# FPGA_SDRAM.net
KiCad netlist of a schematic drawn in Altium Designer
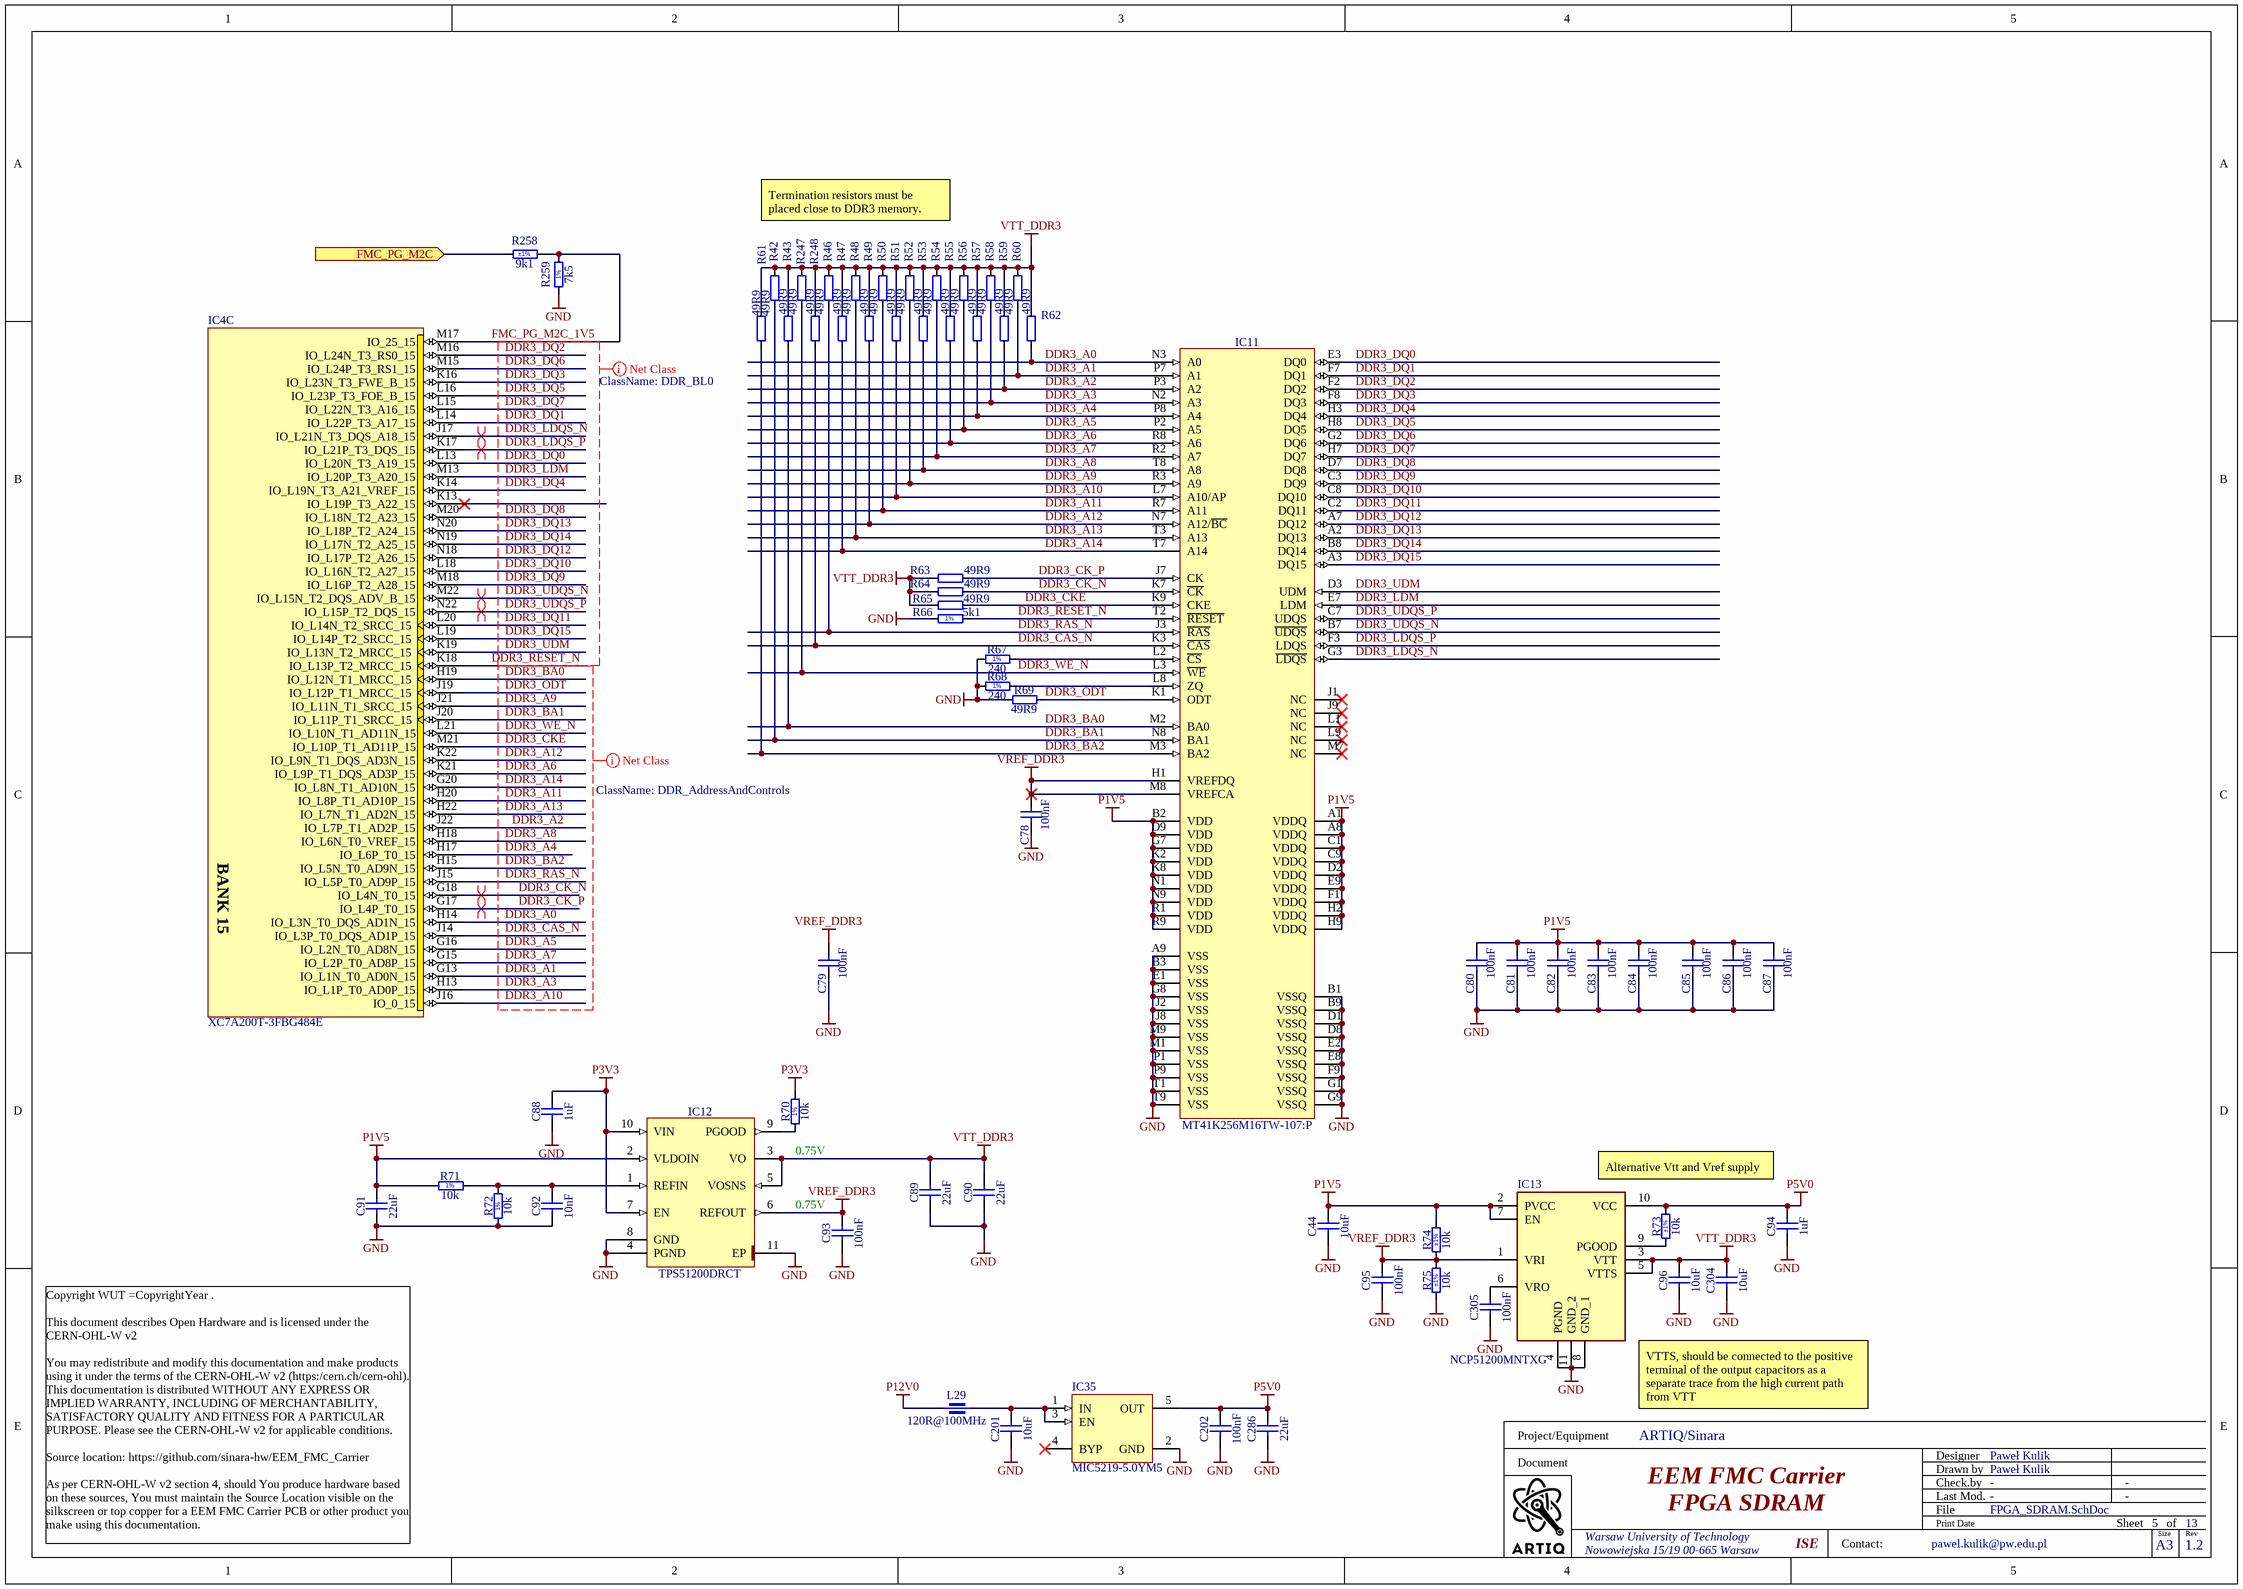
[diagram p0: FPGA_SDRAM.SchDoc]

(export (version "E")
  (design (tool "Eeschema 10.0.6"))
  (components
    (comp (ref "C44")
      (value "10uF")
      (footprint "CAPC2012X95N")
      (description "Non-polarised capacitor")
      (fields
        (field (name "PART NUMBER") "CC0805_10UF_25V_10%_X5R")
        (field (name "VOLTAGE") "25V")
        (field (name "AUTHOR") "CERN DEM JLC")
      )
      (libsource (lib "Capacitors") (part "Capacitor - non polarized"))
    )
    (comp (ref "C78")
      (value "100nF")
      (footprint "CAPC0603X33N")
      (description "Non-polarised capacitor")
      (fields
        (field (name "PART NUMBER") "CC0201_100NF_6.3V_10%_X5R")
        (field (name "VOLTAGE") "6.3V")
        (field (name "AUTHOR") "CERN DEM JLC")
      )
      (libsource (lib "Capacitors") (part "Capacitor - non polarized"))
    )
    (comp (ref "C79")
      (value "100nF")
      (footprint "CAPC0603X33N")
      (description "Non-polarised capacitor")
      (fields
        (field (name "PART NUMBER") "CC0201_100NF_6.3V_10%_X5R")
        (field (name "VOLTAGE") "6.3V")
        (field (name "AUTHOR") "CERN DEM JLC")
      )
      (libsource (lib "Capacitors") (part "Capacitor - non polarized"))
    )
    (comp (ref "C80")
      (value "100nF")
      (footprint "CAPC0603X33N")
      (description "Non-polarised capacitor")
      (fields
        (field (name "PART NUMBER") "CC0201_100NF_6.3V_10%_X5R")
        (field (name "VOLTAGE") "6.3V")
        (field (name "AUTHOR") "CERN DEM JLC")
      )
      (libsource (lib "Capacitors") (part "Capacitor - non polarized"))
    )
    (comp (ref "C81")
      (value "100nF")
      (footprint "CAPC0603X33N")
      (description "Non-polarised capacitor")
      (fields
        (field (name "PART NUMBER") "CC0201_100NF_6.3V_10%_X5R")
        (field (name "VOLTAGE") "6.3V")
        (field (name "AUTHOR") "CERN DEM JLC")
      )
      (libsource (lib "Capacitors") (part "Capacitor - non polarized"))
    )
    (comp (ref "C82")
      (value "100nF")
      (footprint "CAPC0603X33N")
      (description "Non-polarised capacitor")
      (fields
        (field (name "PART NUMBER") "CC0201_100NF_6.3V_10%_X5R")
        (field (name "VOLTAGE") "6.3V")
        (field (name "AUTHOR") "CERN DEM JLC")
      )
      (libsource (lib "Capacitors") (part "Capacitor - non polarized"))
    )
    (comp (ref "C83")
      (value "100nF")
      (footprint "CAPC0603X33N")
      (description "Non-polarised capacitor")
      (fields
        (field (name "PART NUMBER") "CC0201_100NF_6.3V_10%_X5R")
        (field (name "VOLTAGE") "6.3V")
        (field (name "AUTHOR") "CERN DEM JLC")
      )
      (libsource (lib "Capacitors") (part "Capacitor - non polarized"))
    )
    (comp (ref "C84")
      (value "100nF")
      (footprint "CAPC0603X33N")
      (description "Non-polarised capacitor")
      (fields
        (field (name "PART NUMBER") "CC0201_100NF_6.3V_10%_X5R")
        (field (name "VOLTAGE") "6.3V")
        (field (name "AUTHOR") "CERN DEM JLC")
      )
      (libsource (lib "Capacitors") (part "Capacitor - non polarized"))
    )
    (comp (ref "C85")
      (value "100nF")
      (footprint "CAPC0603X33N")
      (description "Non-polarised capacitor")
      (fields
        (field (name "PART NUMBER") "CC0201_100NF_6.3V_10%_X5R")
        (field (name "VOLTAGE") "6.3V")
        (field (name "AUTHOR") "CERN DEM JLC")
      )
      (libsource (lib "Capacitors") (part "Capacitor - non polarized"))
    )
    (comp (ref "C86")
      (value "100nF")
      (footprint "CAPC0603X33N")
      (description "Non-polarised capacitor")
      (fields
        (field (name "PART NUMBER") "CC0201_100NF_6.3V_10%_X5R")
        (field (name "VOLTAGE") "6.3V")
        (field (name "AUTHOR") "CERN DEM JLC")
      )
      (libsource (lib "Capacitors") (part "Capacitor - non polarized"))
    )
    (comp (ref "C87")
      (value "100nF")
      (footprint "CAPC0603X33N")
      (description "Non-polarised capacitor")
      (fields
        (field (name "PART NUMBER") "CC0201_100NF_6.3V_10%_X5R")
        (field (name "VOLTAGE") "6.3V")
        (field (name "AUTHOR") "CERN DEM JLC")
      )
      (libsource (lib "Capacitors") (part "Capacitor - non polarized"))
    )
    (comp (ref "C88")
      (value "1uF")
      (footprint "CAPC1005X55N")
      (description "Non-polarised capacitor")
      (fields
        (field (name "PART NUMBER") "CC0402_1UF_16V_10%_X5R")
        (field (name "VOLTAGE") "16V")
        (field (name "AUTHOR") "CERN DEM JLC")
      )
      (libsource (lib "Capacitors") (part "Capacitor - non polarized"))
    )
    (comp (ref "C89")
      (value "22uF")
      (footprint "CAPC1608X90N")
      (description "Non-polarised capacitor")
      (fields
        (field (name "PART NUMBER") "CC0603_22UF_6.3V_20%_X5R")
        (field (name "VOLTAGE") "6.3V")
        (field (name "AUTHOR") "CERN DEM JLC")
      )
      (libsource (lib "Capacitors") (part "Capacitor - non polarized"))
    )
    (comp (ref "C90")
      (value "22uF")
      (footprint "CAPC1608X90N")
      (description "Non-polarised capacitor")
      (fields
        (field (name "PART NUMBER") "CC0603_22UF_6.3V_20%_X5R")
        (field (name "VOLTAGE") "6.3V")
        (field (name "AUTHOR") "CERN DEM JLC")
      )
      (libsource (lib "Capacitors") (part "Capacitor - non polarized"))
    )
    (comp (ref "C91")
      (value "22uF")
      (footprint "CAPC1608X90N")
      (description "Non-polarised capacitor")
      (fields
        (field (name "PART NUMBER") "CC0603_22UF_6.3V_20%_X5R")
        (field (name "VOLTAGE") "6.3V")
        (field (name "AUTHOR") "CERN DEM JLC")
      )
      (libsource (lib "Capacitors") (part "Capacitor - non polarized"))
    )
    (comp (ref "C92")
      (value "10nF")
      (footprint "CAPC1005X55N")
      (description "Non-polarised capacitor")
      (fields
        (field (name "PART NUMBER") "CC0402_10NF_16V_10%_X7R")
        (field (name "VOLTAGE") "16V")
        (field (name "AUTHOR") "CERN DEM JLC")
      )
      (libsource (lib "Capacitors") (part "Capacitor - non polarized"))
    )
    (comp (ref "C93")
      (value "100nF")
      (footprint "CAPC0603X33N")
      (description "Non-polarised capacitor")
      (fields
        (field (name "PART NUMBER") "CC0201_100NF_6.3V_10%_X5R")
        (field (name "VOLTAGE") "6.3V")
        (field (name "AUTHOR") "CERN DEM JLC")
      )
      (libsource (lib "Capacitors") (part "Capacitor - non polarized"))
    )
    (comp (ref "C94")
      (value "1uF")
      (footprint "CAPC1608X87N")
      (description "Non-polarised capacitor")
      (fields
        (field (name "PART NUMBER") "CC0603_1UF_25V_10%_X7R")
        (field (name "VOLTAGE") "25V")
        (field (name "AUTHOR") "CERN DEM JLC")
      )
      (libsource (lib "Capacitors") (part "Capacitor - non polarized"))
    )
    (comp (ref "C95")
      (value "100nF")
      (footprint "CAPC0603X33N")
      (description "Non-polarised capacitor")
      (fields
        (field (name "PART NUMBER") "CC0201_100NF_6.3V_10%_X5R")
        (field (name "VOLTAGE") "6.3V")
        (field (name "AUTHOR") "CERN DEM JLC")
      )
      (libsource (lib "Capacitors") (part "Capacitor - non polarized"))
    )
    (comp (ref "C96")
      (value "10uF")
      (footprint "CAPC2012X95N")
      (description "Non-polarised capacitor")
      (fields
        (field (name "PART NUMBER") "CC0805_10UF_25V_10%_X5R")
        (field (name "VOLTAGE") "25V")
        (field (name "AUTHOR") "CERN DEM JLC")
      )
      (libsource (lib "Capacitors") (part "Capacitor - non polarized"))
    )
    (comp (ref "C201")
      (value "10uF")
      (footprint "CAPC2012X95N")
      (description "Non-polarised capacitor")
      (fields
        (field (name "PART NUMBER") "CC0805_10UF_25V_10%_X5R")
        (field (name "VOLTAGE") "25V")
        (field (name "AUTHOR") "CERN DEM JLC")
      )
      (libsource (lib "Capacitors") (part "Capacitor - non polarized"))
    )
    (comp (ref "C202")
      (value "100nF")
      (footprint "CAPC0603X33N")
      (description "Non-polarised capacitor")
      (fields
        (field (name "PART NUMBER") "CC0201_100NF_6.3V_10%_X5R")
        (field (name "VOLTAGE") "6.3V")
        (field (name "AUTHOR") "CERN DEM JLC")
      )
      (libsource (lib "Capacitors") (part "Capacitor - non polarized"))
    )
    (comp (ref "C286")
      (value "22uF")
      (footprint "CAPC1608X90N")
      (description "Non-polarised capacitor")
      (fields
        (field (name "PART NUMBER") "CC0603_22UF_6.3V_20%_X5R")
        (field (name "VOLTAGE") "6.3V")
        (field (name "AUTHOR") "CERN DEM JLC")
      )
      (libsource (lib "Capacitors") (part "Capacitor - non polarized"))
    )
    (comp (ref "C304")
      (value "10uF")
      (footprint "CAPC2012X95N")
      (description "Non-polarised capacitor")
      (fields
        (field (name "PART NUMBER") "CC0805_10UF_25V_10%_X5R")
        (field (name "VOLTAGE") "25V")
        (field (name "AUTHOR") "CERN DEM JLC")
      )
      (libsource (lib "Capacitors") (part "Capacitor - non polarized"))
    )
    (comp (ref "C305")
      (value "100nF")
      (footprint "CAPC0603X33N")
      (description "Non-polarised capacitor")
      (fields
        (field (name "PART NUMBER") "CC0201_100NF_6.3V_10%_X5R")
        (field (name "VOLTAGE") "6.3V")
        (field (name "AUTHOR") "CERN DEM JLC")
      )
      (libsource (lib "Capacitors") (part "Capacitor - non polarized"))
    )
    (comp (ref "IC4")
      (value "XC7A200T-3FBG484E")
      (footprint "BGA484C100P22X22_2300X2300X254")
      (description "Artix-7 FPGA, 285 User I/Os, 4 GTP, 484-Ball BGA, Pb-Free")
      (libsource (lib "Integrated_Library_LOADER") (part "XC7A200T-3FBG484E"))
    )
    (comp (ref "IC11")
      (value "MT41K256M16TW-107:P")
      (footprint "BGA96C80P9X16_800X1400X120")
      (description "32 Meg x 16 x 8 Banks DDR3L SDRAM")
      (fields (field (name "MANUFACTURER") "MICRON TECHNOLOGY") (field (name "AUTHOR") "CERN DEM MR"))
      (libsource (lib "ICs And Semiconductors") (part "MT41K256M16TW-107{colon}P"))
    )
    (comp (ref "IC12")
      (value "TPS51200DRCT")
      (footprint "TEXAS_DRC (S-PVSON-N10)")
      (description "Sink/Source DDR Termination Regulator")
      (fields (field (name "MANUFACTURER") "TEXAS INSTRUMENTS") (field (name "AUTHOR") "CERN DEM JLC"))
      (libsource (lib "ICs And Semiconductors") (part "TPS51200DRC"))
    )
    (comp (ref "IC13")
      (value "NCP51200MNTXG")
      (footprint "SON50P300X300X100-11N")
      (description "Integrated Circuit")
      (fields (field (name "MOUSER PART NUMBER") "863-NCP51200MNTXG"))
      (libsource (lib "Integrated_Library_LOADER") (part "NCP51200MNTXG"))
    )
    (comp (ref "IC35")
      (value "MIC5219-5.0YM5")
      (footprint "SOT95P280X145-5N")
      (description "500mA-Peak Output LDO Regulator 5.0V")
      (fields (field (name "MANUFACTURER") "Microchip"))
      (libsource (lib "Schlib1") (part "MIC5219-5.0YM5"))
    )
    (comp (ref "L29")
      (value "120R@100MHz")
      (footprint "INDC1608X65N")
      (fields
        (field (name "PART NUMBER") "IND0603_MURATA_BLM18SG121TN1D")
        (field (name "POWER") "3A")
        (field (name "MANUFACTURER") "MURATA")
        (field (name "AUTHOR") "CERN DEM JLC")
      )
      (libsource (lib "Inductors & Transformers") (part "Ferrite Bead"))
    )
    (comp (ref "R42")
      (value "49R9")
      (footprint "RESC1005X40N")
      (description "Resistor - 1%")
      (fields
        (field (name "PART NUMBER") "R0402_49R9_1%_0.0625W_100PPM")
        (field (name "POWER") "0.0625W")
        (field (name "AUTHOR") "CERN DEM JLC")
      )
      (libsource (lib "Resistors") (part "Resistor - 1%"))
    )
    (comp (ref "R43")
      (value "49R9")
      (footprint "RESC1005X40N")
      (description "Resistor - 1%")
      (fields
        (field (name "PART NUMBER") "R0402_49R9_1%_0.0625W_100PPM")
        (field (name "POWER") "0.0625W")
        (field (name "AUTHOR") "CERN DEM JLC")
      )
      (libsource (lib "Resistors") (part "Resistor - 1%"))
    )
    (comp (ref "R46")
      (value "49R9")
      (footprint "RESC1005X40N")
      (description "Resistor - 1%")
      (fields
        (field (name "PART NUMBER") "R0402_49R9_1%_0.0625W_100PPM")
        (field (name "POWER") "0.0625W")
        (field (name "AUTHOR") "CERN DEM JLC")
      )
      (libsource (lib "Resistors") (part "Resistor - 1%"))
    )
    (comp (ref "R47")
      (value "49R9")
      (footprint "RESC1005X40N")
      (description "Resistor - 1%")
      (fields
        (field (name "PART NUMBER") "R0402_49R9_1%_0.0625W_100PPM")
        (field (name "POWER") "0.0625W")
        (field (name "AUTHOR") "CERN DEM JLC")
      )
      (libsource (lib "Resistors") (part "Resistor - 1%"))
    )
    (comp (ref "R48")
      (value "49R9")
      (footprint "RESC1005X40N")
      (description "Resistor - 1%")
      (fields
        (field (name "PART NUMBER") "R0402_49R9_1%_0.0625W_100PPM")
        (field (name "POWER") "0.0625W")
        (field (name "AUTHOR") "CERN DEM JLC")
      )
      (libsource (lib "Resistors") (part "Resistor - 1%"))
    )
    (comp (ref "R49")
      (value "49R9")
      (footprint "RESC1005X40N")
      (description "Resistor - 1%")
      (fields
        (field (name "PART NUMBER") "R0402_49R9_1%_0.0625W_100PPM")
        (field (name "POWER") "0.0625W")
        (field (name "AUTHOR") "CERN DEM JLC")
      )
      (libsource (lib "Resistors") (part "Resistor - 1%"))
    )
    (comp (ref "R50")
      (value "49R9")
      (footprint "RESC1005X40N")
      (description "Resistor - 1%")
      (fields
        (field (name "PART NUMBER") "R0402_49R9_1%_0.0625W_100PPM")
        (field (name "POWER") "0.0625W")
        (field (name "AUTHOR") "CERN DEM JLC")
      )
      (libsource (lib "Resistors") (part "Resistor - 1%"))
    )
    (comp (ref "R51")
      (value "49R9")
      (footprint "RESC1005X40N")
      (description "Resistor - 1%")
      (fields
        (field (name "PART NUMBER") "R0402_49R9_1%_0.0625W_100PPM")
        (field (name "POWER") "0.0625W")
        (field (name "AUTHOR") "CERN DEM JLC")
      )
      (libsource (lib "Resistors") (part "Resistor - 1%"))
    )
    (comp (ref "R52")
      (value "49R9")
      (footprint "RESC1005X40N")
      (description "Resistor - 1%")
      (fields
        (field (name "PART NUMBER") "R0402_49R9_1%_0.0625W_100PPM")
        (field (name "POWER") "0.0625W")
        (field (name "AUTHOR") "CERN DEM JLC")
      )
      (libsource (lib "Resistors") (part "Resistor - 1%"))
    )
    (comp (ref "R53")
      (value "49R9")
      (footprint "RESC1005X40N")
      (description "Resistor - 1%")
      (fields
        (field (name "PART NUMBER") "R0402_49R9_1%_0.0625W_100PPM")
        (field (name "POWER") "0.0625W")
        (field (name "AUTHOR") "CERN DEM JLC")
      )
      (libsource (lib "Resistors") (part "Resistor - 1%"))
    )
    (comp (ref "R54")
      (value "49R9")
      (footprint "RESC1005X40N")
      (description "Resistor - 1%")
      (fields
        (field (name "PART NUMBER") "R0402_49R9_1%_0.0625W_100PPM")
        (field (name "POWER") "0.0625W")
        (field (name "AUTHOR") "CERN DEM JLC")
      )
      (libsource (lib "Resistors") (part "Resistor - 1%"))
    )
    (comp (ref "R55")
      (value "49R9")
      (footprint "RESC1005X40N")
      (description "Resistor - 1%")
      (fields
        (field (name "PART NUMBER") "R0402_49R9_1%_0.0625W_100PPM")
        (field (name "POWER") "0.0625W")
        (field (name "AUTHOR") "CERN DEM JLC")
      )
      (libsource (lib "Resistors") (part "Resistor - 1%"))
    )
    (comp (ref "R56")
      (value "49R9")
      (footprint "RESC1005X40N")
      (description "Resistor - 1%")
      (fields
        (field (name "PART NUMBER") "R0402_49R9_1%_0.0625W_100PPM")
        (field (name "POWER") "0.0625W")
        (field (name "AUTHOR") "CERN DEM JLC")
      )
      (libsource (lib "Resistors") (part "Resistor - 1%"))
    )
    (comp (ref "R57")
      (value "49R9")
      (footprint "RESC1005X40N")
      (description "Resistor - 1%")
      (fields
        (field (name "PART NUMBER") "R0402_49R9_1%_0.0625W_100PPM")
        (field (name "POWER") "0.0625W")
        (field (name "AUTHOR") "CERN DEM JLC")
      )
      (libsource (lib "Resistors") (part "Resistor - 1%"))
    )
    (comp (ref "R58")
      (value "49R9")
      (footprint "RESC1005X40N")
      (description "Resistor - 1%")
      (fields
        (field (name "PART NUMBER") "R0402_49R9_1%_0.0625W_100PPM")
        (field (name "POWER") "0.0625W")
        (field (name "AUTHOR") "CERN DEM JLC")
      )
      (libsource (lib "Resistors") (part "Resistor - 1%"))
    )
    (comp (ref "R59")
      (value "49R9")
      (footprint "RESC1005X40N")
      (description "Resistor - 1%")
      (fields
        (field (name "PART NUMBER") "R0402_49R9_1%_0.0625W_100PPM")
        (field (name "POWER") "0.0625W")
        (field (name "AUTHOR") "CERN DEM JLC")
      )
      (libsource (lib "Resistors") (part "Resistor - 1%"))
    )
    (comp (ref "R60")
      (value "49R9")
      (footprint "RESC1005X40N")
      (description "Resistor - 1%")
      (fields
        (field (name "PART NUMBER") "R0402_49R9_1%_0.0625W_100PPM")
        (field (name "POWER") "0.0625W")
        (field (name "AUTHOR") "CERN DEM JLC")
      )
      (libsource (lib "Resistors") (part "Resistor - 1%"))
    )
    (comp (ref "R61")
      (value "49R9")
      (footprint "RESC1005X40N")
      (description "Resistor - 1%")
      (fields
        (field (name "PART NUMBER") "R0402_49R9_1%_0.0625W_100PPM")
        (field (name "POWER") "0.0625W")
        (field (name "AUTHOR") "CERN DEM JLC")
      )
      (libsource (lib "Resistors") (part "Resistor - 1%"))
    )
    (comp (ref "R62")
      (value "49R9")
      (footprint "RESC1005X40N")
      (description "Resistor - 1%")
      (fields
        (field (name "PART NUMBER") "R0402_49R9_1%_0.0625W_100PPM")
        (field (name "POWER") "0.0625W")
        (field (name "AUTHOR") "CERN DEM JLC")
      )
      (libsource (lib "Resistors") (part "Resistor - 1%"))
    )
    (comp (ref "R63")
      (value "49R9")
      (footprint "RESC1005X40N")
      (description "Resistor - 1%")
      (fields
        (field (name "PART NUMBER") "R0402_49R9_1%_0.0625W_100PPM")
        (field (name "POWER") "0.0625W")
        (field (name "AUTHOR") "CERN DEM JLC")
      )
      (libsource (lib "Resistors") (part "Resistor - 1%"))
    )
    (comp (ref "R64")
      (value "49R9")
      (footprint "RESC1005X40N")
      (description "Resistor - 1%")
      (fields
        (field (name "PART NUMBER") "R0402_49R9_1%_0.0625W_100PPM")
        (field (name "POWER") "0.0625W")
        (field (name "AUTHOR") "CERN DEM JLC")
      )
      (libsource (lib "Resistors") (part "Resistor - 1%"))
    )
    (comp (ref "R65")
      (value "49R9")
      (footprint "RESC1005X40N")
      (description "Resistor - 1%")
      (fields
        (field (name "PART NUMBER") "R0402_49R9_1%_0.0625W_100PPM")
        (field (name "POWER") "0.0625W")
        (field (name "AUTHOR") "CERN DEM JLC")
      )
      (libsource (lib "Resistors") (part "Resistor - 1%"))
    )
    (comp (ref "R66")
      (value "5k1")
      (footprint "RESC1005X40N")
      (description "Resistor - 1%")
      (fields
        (field (name "PART NUMBER") "R0402_5K1_1%_0.0625W_100PPM")
        (field (name "POWER") "0.0625W")
        (field (name "AUTHOR") "CERN DEM JLC")
      )
      (libsource (lib "Resistors") (part "Resistor - 1%"))
    )
    (comp (ref "R67")
      (value "240")
      (footprint "RESC1005X40N")
      (description "Resistor - 1%")
      (fields
        (field (name "PART NUMBER") "R0402_240R_1%_0.0625W_100PPM")
        (field (name "POWER") "0.0625W")
        (field (name "AUTHOR") "CERN DEM JLC")
      )
      (libsource (lib "Resistors") (part "Resistor - 1%"))
    )
    (comp (ref "R68")
      (value "240")
      (footprint "RESC1005X40N")
      (description "Resistor - 1%")
      (fields
        (field (name "PART NUMBER") "R0402_240R_1%_0.0625W_100PPM")
        (field (name "POWER") "0.0625W")
        (field (name "AUTHOR") "CERN DEM JLC")
      )
      (libsource (lib "Resistors") (part "Resistor - 1%"))
    )
    (comp (ref "R69")
      (value "49R9")
      (footprint "RESC1005X40N")
      (description "Resistor - 1%")
      (fields
        (field (name "PART NUMBER") "R0402_49R9_1%_0.0625W_100PPM")
        (field (name "POWER") "0.0625W")
        (field (name "AUTHOR") "CERN DEM JLC")
      )
      (libsource (lib "Resistors") (part "Resistor - 1%"))
    )
    (comp (ref "R70")
      (value "10k")
      (footprint "RESC1005X40N")
      (description "Resistor - 1%")
      (fields
        (field (name "PART NUMBER") "R0402_10K_1%_0.0625W_100PPM")
        (field (name "POWER") "0.0625W")
        (field (name "AUTHOR") "CERN DEM JLC")
      )
      (libsource (lib "Resistors") (part "Resistor - 1%"))
    )
    (comp (ref "R71")
      (value "10k")
      (footprint "RESC1005X40N")
      (description "Resistor - 1%")
      (fields
        (field (name "PART NUMBER") "R0402_10K_1%_0.0625W_100PPM")
        (field (name "POWER") "0.0625W")
        (field (name "AUTHOR") "CERN DEM JLC")
      )
      (libsource (lib "Resistors") (part "Resistor - 1%"))
    )
    (comp (ref "R72")
      (value "10k")
      (footprint "RESC1005X40N")
      (description "Resistor - 1%")
      (fields
        (field (name "PART NUMBER") "R0402_10K_1%_0.0625W_100PPM")
        (field (name "POWER") "0.0625W")
        (field (name "AUTHOR") "CERN DEM JLC")
      )
      (libsource (lib "Resistors") (part "Resistor - 1%"))
    )
    (comp (ref "R73")
      (value "10k")
      (footprint "RESC1005X40N")
      (description "Resistor - 1%")
      (fields
        (field (name "TOLERANCE") "±1%")
        (field (name "PART NUMBER") "R0402_10K_1%_0.0625W_100PPM")
        (field (name "POWER") "0.0625W")
        (field (name "AUTHOR") "CERN DEM JLC")
      )
      (libsource (lib "Resistors") (part "Resistor - 1%"))
    )
    (comp (ref "R74")
      (value "10k")
      (footprint "RESC1005X40N")
      (description "Resistor - 1%")
      (fields
        (field (name "TOLERANCE") "±1%")
        (field (name "PART NUMBER") "R0402_10K_1%_0.0625W_100PPM")
        (field (name "POWER") "0.0625W")
        (field (name "AUTHOR") "CERN DEM JLC")
      )
      (libsource (lib "Resistors") (part "Resistor - 1%"))
    )
    (comp (ref "R75")
      (value "10k")
      (footprint "RESC1005X40N")
      (description "Resistor - 1%")
      (fields
        (field (name "TOLERANCE") "±1%")
        (field (name "PART NUMBER") "R0402_10K_1%_0.0625W_100PPM")
        (field (name "POWER") "0.0625W")
        (field (name "AUTHOR") "CERN DEM JLC")
      )
      (libsource (lib "Resistors") (part "Resistor - 1%"))
    )
    (comp (ref "R247")
      (value "49R9")
      (footprint "RESC1005X40N")
      (description "Resistor - 1%")
      (fields
        (field (name "PART NUMBER") "R0402_49R9_1%_0.0625W_100PPM")
        (field (name "POWER") "0.0625W")
        (field (name "AUTHOR") "CERN DEM JLC")
      )
      (libsource (lib "Resistors") (part "Resistor - 1%"))
    )
    (comp (ref "R248")
      (value "49R9")
      (footprint "RESC1005X40N")
      (description "Resistor - 1%")
      (fields
        (field (name "PART NUMBER") "R0402_49R9_1%_0.0625W_100PPM")
        (field (name "POWER") "0.0625W")
        (field (name "AUTHOR") "CERN DEM JLC")
      )
      (libsource (lib "Resistors") (part "Resistor - 1%"))
    )
    (comp (ref "R258")
      (value "9k1")
      (footprint "RESC1005X40N")
      (description "Resistor - 1%")
      (fields
        (field (name "TOLERANCE") "±1%")
        (field (name "PART NUMBER") "R0402_9K1_1%_0.0625W_100PPM")
        (field (name "POWER") "0.0625W")
        (field (name "AUTHOR") "CERN DEM JLC")
      )
      (libsource (lib "Resistors") (part "Resistor - 1%"))
    )
    (comp (ref "R259")
      (value "7k5")
      (footprint "RESC1005X40N")
      (description "Resistor - 1%")
      (fields
        (field (name "PART NUMBER") "R0402_7K5_1%_0.0625W_100PPM")
        (field (name "POWER") "0.0625W")
        (field (name "AUTHOR") "CERN DEM JLC")
      )
      (libsource (lib "Resistors") (part "Resistor - 1%"))
    )
  )
  (nets
    (net (code "1") (name "/DDR3_A0") (class "Default")
      (node (ref "IC11") (pin "N3") (pinfunction "A0_N3") (pintype "input"))
      (node (ref "IC4") (pin "H14") (pinfunction "IO_L3N_T0_DQS_AD1N_15_H14") (pintype "bidirectional"))
      (node (ref "R62") (pin "1") (pinfunction "1_1") (pintype "passive"))
    )
    (net (code "2") (name "/DDR3_A1") (class "Default")
      (node (ref "IC11") (pin "P7") (pinfunction "A1_P7") (pintype "input"))
      (node (ref "IC4") (pin "G13") (pinfunction "IO_L1N_T0_AD0N_15_G13") (pintype "bidirectional"))
      (node (ref "R60") (pin "1") (pinfunction "1_1") (pintype "passive"))
    )
    (net (code "3") (name "/DDR3_A2") (class "Default")
      (node (ref "IC11") (pin "P3") (pinfunction "A2_P3") (pintype "input"))
      (node (ref "IC4") (pin "J22") (pinfunction "IO_L7P_T1_AD2P_15_J22") (pintype "bidirectional"))
      (node (ref "R59") (pin "1") (pinfunction "1_1") (pintype "passive"))
    )
    (net (code "4") (name "/DDR3_A3") (class "Default")
      (node (ref "IC11") (pin "N2") (pinfunction "A3_N2") (pintype "input"))
      (node (ref "IC4") (pin "H13") (pinfunction "IO_L1P_T0_AD0P_15_H13") (pintype "bidirectional"))
      (node (ref "R58") (pin "1") (pinfunction "1_1") (pintype "passive"))
    )
    (net (code "5") (name "/DDR3_A4") (class "Default")
      (node (ref "IC11") (pin "P8") (pinfunction "A4_P8") (pintype "input"))
      (node (ref "IC4") (pin "H17") (pinfunction "IO_L6P_T0_15_H17") (pintype "bidirectional"))
      (node (ref "R57") (pin "1") (pinfunction "1_1") (pintype "passive"))
    )
    (net (code "6") (name "/DDR3_A5") (class "Default")
      (node (ref "IC11") (pin "P2") (pinfunction "A5_P2") (pintype "input"))
      (node (ref "IC4") (pin "G16") (pinfunction "IO_L2N_T0_AD8N_15_G16") (pintype "bidirectional"))
      (node (ref "R56") (pin "1") (pinfunction "1_1") (pintype "passive"))
    )
    (net (code "7") (name "/DDR3_A6") (class "Default")
      (node (ref "IC11") (pin "R8") (pinfunction "A6_R8") (pintype "input"))
      (node (ref "IC4") (pin "K21") (pinfunction "IO_L9P_T1_DQS_AD3P_15_K21") (pintype "bidirectional"))
      (node (ref "R55") (pin "1") (pinfunction "1_1") (pintype "passive"))
    )
    (net (code "8") (name "/DDR3_A7") (class "Default")
      (node (ref "IC11") (pin "R2") (pinfunction "A7_R2") (pintype "input"))
      (node (ref "IC4") (pin "G15") (pinfunction "IO_L2P_T0_AD8P_15_G15") (pintype "bidirectional"))
      (node (ref "R54") (pin "1") (pinfunction "1_1") (pintype "passive"))
    )
    (net (code "9") (name "/DDR3_A8") (class "Default")
      (node (ref "IC11") (pin "T8") (pinfunction "A8_T8") (pintype "input"))
      (node (ref "IC4") (pin "H18") (pinfunction "IO_L6N_T0_VREF_15_H18") (pintype "bidirectional"))
      (node (ref "R53") (pin "1") (pinfunction "1_1") (pintype "passive"))
    )
    (net (code "10") (name "/DDR3_A9") (class "Default")
      (node (ref "IC11") (pin "R3") (pinfunction "A9_R3") (pintype "input"))
      (node (ref "IC4") (pin "J21") (pinfunction "IO_L11N_T1_SRCC_15_J21") (pintype "bidirectional"))
      (node (ref "R52") (pin "1") (pinfunction "1_1") (pintype "passive"))
    )
    (net (code "11") (name "/DDR3_A10") (class "Default")
      (node (ref "IC11") (pin "L7") (pinfunction "A10/AP_L7") (pintype "input"))
      (node (ref "IC4") (pin "J16") (pinfunction "IO_0_15_J16") (pintype "bidirectional"))
      (node (ref "R51") (pin "1") (pinfunction "1_1") (pintype "passive"))
    )
    (net (code "12") (name "/DDR3_A11") (class "Default")
      (node (ref "IC11") (pin "R7") (pinfunction "A11_R7") (pintype "input"))
      (node (ref "IC4") (pin "H20") (pinfunction "IO_L8P_T1_AD10P_15_H20") (pintype "bidirectional"))
      (node (ref "R50") (pin "1") (pinfunction "1_1") (pintype "passive"))
    )
    (net (code "13") (name "/DDR3_A12") (class "Default")
      (node (ref "IC11") (pin "N7") (pinfunction "A12/~{BC}_N7") (pintype "input"))
      (node (ref "IC4") (pin "K22") (pinfunction "IO_L9N_T1_DQS_AD3N_15_K22") (pintype "bidirectional"))
      (node (ref "R49") (pin "1") (pinfunction "1_1") (pintype "passive"))
    )
    (net (code "14") (name "/DDR3_A13") (class "Default")
      (node (ref "IC11") (pin "T3") (pinfunction "A13_T3") (pintype "input"))
      (node (ref "IC4") (pin "H22") (pinfunction "IO_L7N_T1_AD2N_15_H22") (pintype "bidirectional"))
      (node (ref "R48") (pin "1") (pinfunction "1_1") (pintype "passive"))
    )
    (net (code "15") (name "/DDR3_A14") (class "Default")
      (node (ref "IC11") (pin "T7") (pinfunction "A14_T7") (pintype "passive"))
      (node (ref "IC4") (pin "G20") (pinfunction "IO_L8N_T1_AD10N_15_G20") (pintype "bidirectional"))
      (node (ref "R47") (pin "1") (pinfunction "1_1") (pintype "passive"))
    )
    (net (code "16") (name "/DDR3_BA0") (class "Default")
      (node (ref "IC11") (pin "M2") (pinfunction "BA0_M2") (pintype "input"))
      (node (ref "IC4") (pin "H19") (pinfunction "IO_L12N_T1_MRCC_15_H19") (pintype "bidirectional"))
      (node (ref "R43") (pin "1") (pinfunction "1_1") (pintype "passive"))
    )
    (net (code "17") (name "/DDR3_BA1") (class "Default")
      (node (ref "IC11") (pin "N8") (pinfunction "BA1_N8") (pintype "input"))
      (node (ref "IC4") (pin "J20") (pinfunction "IO_L11P_T1_SRCC_15_J20") (pintype "bidirectional"))
      (node (ref "R42") (pin "1") (pinfunction "1_1") (pintype "passive"))
    )
    (net (code "18") (name "/DDR3_BA2") (class "Default")
      (node (ref "IC11") (pin "M3") (pinfunction "BA2_M3") (pintype "input"))
      (node (ref "IC4") (pin "H15") (pinfunction "IO_L5N_T0_AD9N_15_H15") (pintype "bidirectional"))
      (node (ref "R61") (pin "1") (pinfunction "1_1") (pintype "passive"))
    )
    (net (code "19") (name "/DDR3_CAS_N") (class "Default")
      (node (ref "IC11") (pin "K3") (pinfunction "~{CAS}_K3") (pintype "input"))
      (node (ref "IC4") (pin "J14") (pinfunction "IO_L3P_T0_DQS_AD1P_15_J14") (pintype "bidirectional"))
      (node (ref "R248") (pin "1") (pinfunction "1_1") (pintype "passive"))
    )
    (net (code "20") (name "/DDR3_CKE") (class "Default")
      (node (ref "IC11") (pin "K9") (pinfunction "CKE_K9") (pintype "input"))
      (node (ref "IC4") (pin "M21") (pinfunction "IO_L10P_T1_AD11P_15_M21") (pintype "bidirectional"))
      (node (ref "R65") (pin "2") (pinfunction "2_2") (pintype "passive"))
    )
    (net (code "21") (name "/DDR3_CK_N") (class "Default")
      (node (ref "IC11") (pin "K7") (pinfunction "~{CK}_K7") (pintype "input"))
      (node (ref "IC4") (pin "G18") (pinfunction "IO_L4N_T0_15_G18") (pintype "bidirectional"))
      (node (ref "R64") (pin "2") (pinfunction "2_2") (pintype "passive"))
    )
    (net (code "22") (name "/DDR3_CK_P") (class "Default")
      (node (ref "IC11") (pin "J7") (pinfunction "CK_J7") (pintype "input"))
      (node (ref "IC4") (pin "G17") (pinfunction "IO_L4P_T0_15_G17") (pintype "bidirectional"))
      (node (ref "R63") (pin "2") (pinfunction "2_2") (pintype "passive"))
    )
    (net (code "23") (name "/DDR3_DQ0") (class "Default")
      (node (ref "IC11") (pin "E3") (pinfunction "DQ0_E3") (pintype "bidirectional"))
      (node (ref "IC4") (pin "L13") (pinfunction "IO_L20N_T3_A19_15_L13") (pintype "bidirectional"))
    )
    (net (code "24") (name "/DDR3_DQ1") (class "Default")
      (node (ref "IC11") (pin "F7") (pinfunction "DQ1_F7") (pintype "bidirectional"))
      (node (ref "IC4") (pin "L14") (pinfunction "IO_L22P_T3_A17_15_L14") (pintype "bidirectional"))
    )
    (net (code "25") (name "/DDR3_DQ2") (class "Default")
      (node (ref "IC11") (pin "F2") (pinfunction "DQ2_F2") (pintype "bidirectional"))
      (node (ref "IC4") (pin "M16") (pinfunction "IO_L24N_T3_RS0_15_M16") (pintype "bidirectional"))
    )
    (net (code "26") (name "/DDR3_DQ3") (class "Default")
      (node (ref "IC11") (pin "F8") (pinfunction "DQ3_F8") (pintype "bidirectional"))
      (node (ref "IC4") (pin "K16") (pinfunction "IO_L23N_T3_FWE_B_15_K16") (pintype "bidirectional"))
    )
    (net (code "27") (name "/DDR3_DQ4") (class "Default")
      (node (ref "IC11") (pin "H3") (pinfunction "DQ4_H3") (pintype "bidirectional"))
      (node (ref "IC4") (pin "K14") (pinfunction "IO_L19N_T3_A21_VREF_15_K14") (pintype "bidirectional"))
    )
    (net (code "28") (name "/DDR3_DQ5") (class "Default")
      (node (ref "IC11") (pin "H8") (pinfunction "DQ5_H8") (pintype "bidirectional"))
      (node (ref "IC4") (pin "L16") (pinfunction "IO_L23P_T3_FOE_B_15_L16") (pintype "bidirectional"))
    )
    (net (code "29") (name "/DDR3_DQ6") (class "Default")
      (node (ref "IC11") (pin "G2") (pinfunction "DQ6_G2") (pintype "bidirectional"))
      (node (ref "IC4") (pin "M15") (pinfunction "IO_L24P_T3_RS1_15_M15") (pintype "bidirectional"))
    )
    (net (code "30") (name "/DDR3_DQ7") (class "Default")
      (node (ref "IC11") (pin "H7") (pinfunction "DQ7_H7") (pintype "bidirectional"))
      (node (ref "IC4") (pin "L15") (pinfunction "IO_L22N_T3_A16_15_L15") (pintype "bidirectional"))
    )
    (net (code "31") (name "/DDR3_DQ8") (class "Default")
      (node (ref "IC11") (pin "D7") (pinfunction "DQ8_D7") (pintype "bidirectional"))
      (node (ref "IC4") (pin "M20") (pinfunction "IO_L18N_T2_A23_15_M20") (pintype "bidirectional"))
    )
    (net (code "32") (name "/DDR3_DQ9") (class "Default")
      (node (ref "IC11") (pin "C3") (pinfunction "DQ9_C3") (pintype "bidirectional"))
      (node (ref "IC4") (pin "M18") (pinfunction "IO_L16P_T2_A28_15_M18") (pintype "bidirectional"))
    )
    (net (code "33") (name "/DDR3_DQ10") (class "Default")
      (node (ref "IC11") (pin "C8") (pinfunction "DQ10_C8") (pintype "bidirectional"))
      (node (ref "IC4") (pin "L18") (pinfunction "IO_L16N_T2_A27_15_L18") (pintype "bidirectional"))
    )
    (net (code "34") (name "/DDR3_DQ11") (class "Default")
      (node (ref "IC11") (pin "C2") (pinfunction "DQ11_C2") (pintype "bidirectional"))
      (node (ref "IC4") (pin "L20") (pinfunction "IO_L14N_T2_SRCC_15_L20") (pintype "bidirectional"))
    )
    (net (code "35") (name "/DDR3_DQ12") (class "Default")
      (node (ref "IC11") (pin "A7") (pinfunction "DQ12_A7") (pintype "bidirectional"))
      (node (ref "IC4") (pin "N18") (pinfunction "IO_L17P_T2_A26_15_N18") (pintype "bidirectional"))
    )
    (net (code "36") (name "/DDR3_DQ13") (class "Default")
      (node (ref "IC11") (pin "A2") (pinfunction "DQ13_A2") (pintype "bidirectional"))
      (node (ref "IC4") (pin "N20") (pinfunction "IO_L18P_T2_A24_15_N20") (pintype "bidirectional"))
    )
    (net (code "37") (name "/DDR3_DQ14") (class "Default")
      (node (ref "IC11") (pin "B8") (pinfunction "DQ14_B8") (pintype "bidirectional"))
      (node (ref "IC4") (pin "N19") (pinfunction "IO_L17N_T2_A25_15_N19") (pintype "bidirectional"))
    )
    (net (code "38") (name "/DDR3_DQ15") (class "Default")
      (node (ref "IC11") (pin "A3") (pinfunction "DQ15_A3") (pintype "bidirectional"))
      (node (ref "IC4") (pin "L19") (pinfunction "IO_L14P_T2_SRCC_15_L19") (pintype "bidirectional"))
    )
    (net (code "39") (name "/DDR3_LDM") (class "Default")
      (node (ref "IC11") (pin "E7") (pinfunction "LDM_E7") (pintype "input"))
      (node (ref "IC4") (pin "M13") (pinfunction "IO_L20P_T3_A20_15_M13") (pintype "bidirectional"))
    )
    (net (code "40") (name "/DDR3_LDQS_N") (class "Default")
      (node (ref "IC11") (pin "G3") (pinfunction "~{LDQS}_G3") (pintype "bidirectional"))
      (node (ref "IC4") (pin "J17") (pinfunction "IO_L21N_T3_DQS_A18_15_J17") (pintype "bidirectional"))
    )
    (net (code "41") (name "/DDR3_LDQS_P") (class "Default")
      (node (ref "IC11") (pin "F3") (pinfunction "LDQS_F3") (pintype "bidirectional"))
      (node (ref "IC4") (pin "K17") (pinfunction "IO_L21P_T3_DQS_15_K17") (pintype "bidirectional"))
    )
    (net (code "42") (name "/DDR3_ODT") (class "Default")
      (node (ref "IC11") (pin "K1") (pinfunction "ODT_K1") (pintype "input"))
      (node (ref "IC4") (pin "J19") (pinfunction "IO_L12P_T1_MRCC_15_J19") (pintype "bidirectional"))
      (node (ref "R69") (pin "2") (pinfunction "2_2") (pintype "passive"))
    )
    (net (code "43") (name "/DDR3_RAS_N") (class "Default")
      (node (ref "IC11") (pin "J3") (pinfunction "~{RAS}_J3") (pintype "input"))
      (node (ref "IC4") (pin "J15") (pinfunction "IO_L5P_T0_AD9P_15_J15") (pintype "bidirectional"))
      (node (ref "R46") (pin "1") (pinfunction "1_1") (pintype "passive"))
    )
    (net (code "44") (name "/DDR3_RESET_N") (class "Default")
      (node (ref "IC11") (pin "T2") (pinfunction "~{RESET}_T2") (pintype "input"))
      (node (ref "IC4") (pin "K18") (pinfunction "IO_L13P_T2_MRCC_15_K18") (pintype "bidirectional"))
      (node (ref "R66") (pin "2") (pinfunction "2_2") (pintype "passive"))
    )
    (net (code "45") (name "/DDR3_UDM") (class "Default")
      (node (ref "IC11") (pin "D3") (pinfunction "UDM_D3") (pintype "input"))
      (node (ref "IC4") (pin "K19") (pinfunction "IO_L13N_T2_MRCC_15_K19") (pintype "bidirectional"))
    )
    (net (code "46") (name "/DDR3_UDQS_N") (class "Default")
      (node (ref "IC11") (pin "B7") (pinfunction "~{UDQS}_B7") (pintype "bidirectional"))
      (node (ref "IC4") (pin "M22") (pinfunction "IO_L15N_T2_DQS_ADV_B_15_M22") (pintype "bidirectional"))
    )
    (net (code "47") (name "/DDR3_UDQS_P") (class "Default")
      (node (ref "IC11") (pin "C7") (pinfunction "UDQS_C7") (pintype "bidirectional"))
      (node (ref "IC4") (pin "N22") (pinfunction "IO_L15P_T2_DQS_15_N22") (pintype "bidirectional"))
    )
    (net (code "48") (name "/DDR3_WE_N") (class "Default")
      (node (ref "IC11") (pin "L3") (pinfunction "~{WE}_L3") (pintype "input"))
      (node (ref "IC4") (pin "L21") (pinfunction "IO_L10N_T1_AD11N_15_L21") (pintype "bidirectional"))
      (node (ref "R247") (pin "1") (pinfunction "1_1") (pintype "passive"))
    )
    (net (code "49") (name "/FMC_PG_M2C") (class "Default")
      (node (ref "R258") (pin "1") (pinfunction "1_1") (pintype "passive"))
    )
    (net (code "50") (name "/FMC_PG_M2C_1V5") (class "Default")
      (node (ref "IC4") (pin "M17") (pinfunction "IO_25_15_M17") (pintype "bidirectional"))
      (node (ref "R258") (pin "2") (pinfunction "2_2") (pintype "passive"))
      (node (ref "R259") (pin "2") (pinfunction "2_2") (pintype "passive"))
    )
    (net (code "51") (name "GND") (class "Default")
      (node (ref "C201") (pin "1") (pinfunction "1_1") (pintype "passive"))
      (node (ref "C202") (pin "1") (pinfunction "1_1") (pintype "passive"))
      (node (ref "C286") (pin "1") (pinfunction "1_1") (pintype "passive"))
      (node (ref "C304") (pin "1") (pinfunction "1_1") (pintype "passive"))
      (node (ref "C305") (pin "1") (pinfunction "1_1") (pintype "passive"))
      (node (ref "C44") (pin "1") (pinfunction "1_1") (pintype "passive"))
      (node (ref "C78") (pin "1") (pinfunction "1_1") (pintype "passive"))
      (node (ref "C79") (pin "1") (pinfunction "1_1") (pintype "passive"))
      (node (ref "C80") (pin "1") (pinfunction "1_1") (pintype "passive"))
      (node (ref "C81") (pin "1") (pinfunction "1_1") (pintype "passive"))
      (node (ref "C82") (pin "1") (pinfunction "1_1") (pintype "passive"))
      (node (ref "C83") (pin "1") (pinfunction "1_1") (pintype "passive"))
      (node (ref "C84") (pin "1") (pinfunction "1_1") (pintype "passive"))
      (node (ref "C85") (pin "1") (pinfunction "1_1") (pintype "passive"))
      (node (ref "C86") (pin "1") (pinfunction "1_1") (pintype "passive"))
      (node (ref "C87") (pin "1") (pinfunction "1_1") (pintype "passive"))
      (node (ref "C88") (pin "1") (pinfunction "1_1") (pintype "passive"))
      (node (ref "C89") (pin "1") (pinfunction "1_1") (pintype "passive"))
      (node (ref "C90") (pin "1") (pinfunction "1_1") (pintype "passive"))
      (node (ref "C91") (pin "1") (pinfunction "1_1") (pintype "passive"))
      (node (ref "C92") (pin "1") (pinfunction "1_1") (pintype "passive"))
      (node (ref "C93") (pin "1") (pinfunction "1_1") (pintype "passive"))
      (node (ref "C94") (pin "1") (pinfunction "1_1") (pintype "passive"))
      (node (ref "C95") (pin "1") (pinfunction "1_1") (pintype "passive"))
      (node (ref "C96") (pin "1") (pinfunction "1_1") (pintype "passive"))
      (node (ref "IC11") (pin "A9") (pinfunction "VSS_A9") (pintype "power_in"))
      (node (ref "IC11") (pin "B1") (pinfunction "VSSQ_B1") (pintype "power_in"))
      (node (ref "IC11") (pin "B3") (pinfunction "VSS_B3") (pintype "power_in"))
      (node (ref "IC11") (pin "B9") (pinfunction "VSSQ_B9") (pintype "power_in"))
      (node (ref "IC11") (pin "D1") (pinfunction "VSSQ_D1") (pintype "power_in"))
      (node (ref "IC11") (pin "D8") (pinfunction "VSSQ_D8") (pintype "power_in"))
      (node (ref "IC11") (pin "E1") (pinfunction "VSS_E1") (pintype "power_in"))
      (node (ref "IC11") (pin "E2") (pinfunction "VSSQ_E2") (pintype "power_in"))
      (node (ref "IC11") (pin "E8") (pinfunction "VSSQ_E8") (pintype "power_in"))
      (node (ref "IC11") (pin "F9") (pinfunction "VSSQ_F9") (pintype "power_in"))
      (node (ref "IC11") (pin "G1") (pinfunction "VSSQ_G1") (pintype "power_in"))
      (node (ref "IC11") (pin "G8") (pinfunction "VSS_G8") (pintype "power_in"))
      (node (ref "IC11") (pin "G9") (pinfunction "VSSQ_G9") (pintype "power_in"))
      (node (ref "IC11") (pin "J2") (pinfunction "VSS_J2") (pintype "power_in"))
      (node (ref "IC11") (pin "J8") (pinfunction "VSS_J8") (pintype "power_in"))
      (node (ref "IC11") (pin "M1") (pinfunction "VSS_M1") (pintype "power_in"))
      (node (ref "IC11") (pin "M9") (pinfunction "VSS_M9") (pintype "power_in"))
      (node (ref "IC11") (pin "P1") (pinfunction "VSS_P1") (pintype "power_in"))
      (node (ref "IC11") (pin "P9") (pinfunction "VSS_P9") (pintype "power_in"))
      (node (ref "IC11") (pin "T1") (pinfunction "VSS_T1") (pintype "power_in"))
      (node (ref "IC11") (pin "T9") (pinfunction "VSS_T9") (pintype "power_in"))
      (node (ref "IC12") (pin "11") (pinfunction "EP_11") (pintype "power_in"))
      (node (ref "IC12") (pin "4") (pinfunction "PGND_4") (pintype "power_in"))
      (node (ref "IC12") (pin "8") (pinfunction "GND_8") (pintype "power_in"))
      (node (ref "IC13") (pin "11") (pinfunction "GND_2_11") (pintype "passive"))
      (node (ref "IC13") (pin "4") (pinfunction "PGND_4") (pintype "passive"))
      (node (ref "IC13") (pin "8") (pinfunction "GND_1_8") (pintype "passive"))
      (node (ref "IC35") (pin "2") (pinfunction "GND_2") (pintype "passive"))
      (node (ref "R259") (pin "1") (pinfunction "1_1") (pintype "passive"))
      (node (ref "R66") (pin "1") (pinfunction "1_1") (pintype "passive"))
      (node (ref "R67") (pin "1") (pinfunction "1_1") (pintype "passive"))
      (node (ref "R68") (pin "1") (pinfunction "1_1") (pintype "passive"))
      (node (ref "R69") (pin "1") (pinfunction "1_1") (pintype "passive"))
      (node (ref "R72") (pin "1") (pinfunction "1_1") (pintype "passive"))
      (node (ref "R75") (pin "1") (pinfunction "1_1") (pintype "passive"))
    )
    (net (code "52") (name "Net-(IC11-ZQ)") (class "Default")
      (node (ref "IC11") (pin "L8") (pinfunction "ZQ_L8") (pintype "input"))
      (node (ref "R68") (pin "2") (pinfunction "2_2") (pintype "passive"))
    )
    (net (code "53") (name "Net-(IC11-~{CS})") (class "Default")
      (node (ref "IC11") (pin "L2") (pinfunction "~{CS}_L2") (pintype "input"))
      (node (ref "R67") (pin "2") (pinfunction "2_2") (pintype "passive"))
    )
    (net (code "54") (name "Net-(IC12-PGOOD)") (class "Default")
      (node (ref "IC12") (pin "9") (pinfunction "PGOOD_9") (pintype "output"))
      (node (ref "R70") (pin "1") (pinfunction "1_1") (pintype "passive"))
    )
    (net (code "55") (name "Net-(IC12-REFIN)") (class "Default")
      (node (ref "C92") (pin "2") (pinfunction "2_2") (pintype "passive"))
      (node (ref "IC12") (pin "1") (pinfunction "REFIN_1") (pintype "input"))
      (node (ref "R71") (pin "2") (pinfunction "2_2") (pintype "passive"))
      (node (ref "R72") (pin "2") (pinfunction "2_2") (pintype "passive"))
    )
    (net (code "56") (name "Net-(IC13-PGOOD)") (class "Default")
      (node (ref "IC13") (pin "9") (pinfunction "PGOOD_9") (pintype "passive"))
      (node (ref "R73") (pin "1") (pinfunction "1_1") (pintype "passive"))
    )
    (net (code "57") (name "Net-(IC13-VRO)") (class "Default")
      (node (ref "C305") (pin "2") (pinfunction "2_2") (pintype "passive"))
      (node (ref "IC13") (pin "6") (pinfunction "VRO_6") (pintype "passive"))
    )
    (net (code "58") (name "Net-(IC35-EN)") (class "Default")
      (node (ref "C201") (pin "2") (pinfunction "2_2") (pintype "passive"))
      (node (ref "IC35") (pin "1") (pinfunction "IN_1") (pintype "input"))
      (node (ref "IC35") (pin "3") (pinfunction "EN_3") (pintype "input"))
      (node (ref "L29") (pin "2") (pinfunction "2_2") (pintype "passive"))
    )
    (net (code "59") (name "P1V5") (class "Default")
      (node (ref "C44") (pin "2") (pinfunction "2_2") (pintype "passive"))
      (node (ref "C80") (pin "2") (pinfunction "2_2") (pintype "passive"))
      (node (ref "C81") (pin "2") (pinfunction "2_2") (pintype "passive"))
      (node (ref "C82") (pin "2") (pinfunction "2_2") (pintype "passive"))
      (node (ref "C83") (pin "2") (pinfunction "2_2") (pintype "passive"))
      (node (ref "C84") (pin "2") (pinfunction "2_2") (pintype "passive"))
      (node (ref "C85") (pin "2") (pinfunction "2_2") (pintype "passive"))
      (node (ref "C86") (pin "2") (pinfunction "2_2") (pintype "passive"))
      (node (ref "C87") (pin "2") (pinfunction "2_2") (pintype "passive"))
      (node (ref "C91") (pin "2") (pinfunction "2_2") (pintype "passive"))
      (node (ref "IC11") (pin "A1") (pinfunction "VDDQ_A1") (pintype "power_in"))
      (node (ref "IC11") (pin "A8") (pinfunction "VDDQ_A8") (pintype "power_in"))
      (node (ref "IC11") (pin "B2") (pinfunction "VDD_B2") (pintype "power_in"))
      (node (ref "IC11") (pin "C1") (pinfunction "VDDQ_C1") (pintype "power_in"))
      (node (ref "IC11") (pin "C9") (pinfunction "VDDQ_C9") (pintype "power_in"))
      (node (ref "IC11") (pin "D2") (pinfunction "VDDQ_D2") (pintype "power_in"))
      (node (ref "IC11") (pin "D9") (pinfunction "VDD_D9") (pintype "power_in"))
      (node (ref "IC11") (pin "E9") (pinfunction "VDDQ_E9") (pintype "power_in"))
      (node (ref "IC11") (pin "F1") (pinfunction "VDDQ_F1") (pintype "power_in"))
      (node (ref "IC11") (pin "G7") (pinfunction "VDD_G7") (pintype "power_in"))
      (node (ref "IC11") (pin "H2") (pinfunction "VDDQ_H2") (pintype "power_in"))
      (node (ref "IC11") (pin "H9") (pinfunction "VDDQ_H9") (pintype "power_in"))
      (node (ref "IC11") (pin "K2") (pinfunction "VDD_K2") (pintype "power_in"))
      (node (ref "IC11") (pin "K8") (pinfunction "VDD_K8") (pintype "power_in"))
      (node (ref "IC11") (pin "N1") (pinfunction "VDD_N1") (pintype "power_in"))
      (node (ref "IC11") (pin "N9") (pinfunction "VDD_N9") (pintype "power_in"))
      (node (ref "IC11") (pin "R1") (pinfunction "VDD_R1") (pintype "power_in"))
      (node (ref "IC11") (pin "R9") (pinfunction "VDD_R9") (pintype "power_in"))
      (node (ref "IC12") (pin "2") (pinfunction "VLDOIN_2") (pintype "input"))
      (node (ref "IC13") (pin "2") (pinfunction "PVCC_2") (pintype "passive"))
      (node (ref "IC13") (pin "7") (pinfunction "EN_7") (pintype "passive"))
      (node (ref "R71") (pin "1") (pinfunction "1_1") (pintype "passive"))
      (node (ref "R74") (pin "2") (pinfunction "2_2") (pintype "passive"))
    )
    (net (code "60") (name "P3V3") (class "Default")
      (node (ref "C88") (pin "2") (pinfunction "2_2") (pintype "passive"))
      (node (ref "IC12") (pin "10") (pinfunction "VIN_10") (pintype "input"))
      (node (ref "IC12") (pin "7") (pinfunction "EN_7") (pintype "input"))
      (node (ref "R70") (pin "2") (pinfunction "2_2") (pintype "passive"))
    )
    (net (code "61") (name "P5V0") (class "Default")
      (node (ref "C202") (pin "2") (pinfunction "2_2") (pintype "passive"))
      (node (ref "C286") (pin "2") (pinfunction "2_2") (pintype "passive"))
      (node (ref "C94") (pin "2") (pinfunction "2_2") (pintype "passive"))
      (node (ref "IC13") (pin "10") (pinfunction "VCC_10") (pintype "passive"))
      (node (ref "IC35") (pin "5") (pinfunction "OUT_5") (pintype "power_in"))
      (node (ref "R73") (pin "2") (pinfunction "2_2") (pintype "passive"))
    )
    (net (code "62") (name "P12V0") (class "Default")
      (node (ref "L29") (pin "1") (pinfunction "1_1") (pintype "passive"))
    )
    (net (code "63") (name "VREF_DDR3") (class "Default")
      (node (ref "C78") (pin "2") (pinfunction "2_2") (pintype "passive"))
      (node (ref "C79") (pin "2") (pinfunction "2_2") (pintype "passive"))
      (node (ref "C93") (pin "2") (pinfunction "2_2") (pintype "passive"))
      (node (ref "C95") (pin "2") (pinfunction "2_2") (pintype "passive"))
      (node (ref "IC11") (pin "H1") (pinfunction "VREFDQ_H1") (pintype "power_in"))
      (node (ref "IC11") (pin "M8") (pinfunction "VREFCA_M8") (pintype "power_in"))
      (node (ref "IC12") (pin "6") (pinfunction "REFOUT_6") (pintype "output"))
      (node (ref "IC13") (pin "1") (pinfunction "VRI_1") (pintype "passive"))
      (node (ref "R74") (pin "1") (pinfunction "1_1") (pintype "passive"))
      (node (ref "R75") (pin "2") (pinfunction "2_2") (pintype "passive"))
    )
    (net (code "64") (name "VTT_DDR3") (class "Default")
      (node (ref "C304") (pin "2") (pinfunction "2_2") (pintype "passive"))
      (node (ref "C89") (pin "2") (pinfunction "2_2") (pintype "passive"))
      (node (ref "C90") (pin "2") (pinfunction "2_2") (pintype "passive"))
      (node (ref "C96") (pin "2") (pinfunction "2_2") (pintype "passive"))
      (node (ref "IC12") (pin "3") (pinfunction "VO_3") (pintype "power_in"))
      (node (ref "IC12") (pin "5") (pinfunction "VOSNS_5") (pintype "input"))
      (node (ref "IC13") (pin "3") (pinfunction "VTT_3") (pintype "passive"))
      (node (ref "IC13") (pin "5") (pinfunction "VTTS_5") (pintype "passive"))
      (node (ref "R247") (pin "2") (pinfunction "2_2") (pintype "passive"))
      (node (ref "R248") (pin "2") (pinfunction "2_2") (pintype "passive"))
      (node (ref "R42") (pin "2") (pinfunction "2_2") (pintype "passive"))
      (node (ref "R43") (pin "2") (pinfunction "2_2") (pintype "passive"))
      (node (ref "R46") (pin "2") (pinfunction "2_2") (pintype "passive"))
      (node (ref "R47") (pin "2") (pinfunction "2_2") (pintype "passive"))
      (node (ref "R48") (pin "2") (pinfunction "2_2") (pintype "passive"))
      (node (ref "R49") (pin "2") (pinfunction "2_2") (pintype "passive"))
      (node (ref "R50") (pin "2") (pinfunction "2_2") (pintype "passive"))
      (node (ref "R51") (pin "2") (pinfunction "2_2") (pintype "passive"))
      (node (ref "R52") (pin "2") (pinfunction "2_2") (pintype "passive"))
      (node (ref "R53") (pin "2") (pinfunction "2_2") (pintype "passive"))
      (node (ref "R54") (pin "2") (pinfunction "2_2") (pintype "passive"))
      (node (ref "R55") (pin "2") (pinfunction "2_2") (pintype "passive"))
      (node (ref "R56") (pin "2") (pinfunction "2_2") (pintype "passive"))
      (node (ref "R57") (pin "2") (pinfunction "2_2") (pintype "passive"))
      (node (ref "R58") (pin "2") (pinfunction "2_2") (pintype "passive"))
      (node (ref "R59") (pin "2") (pinfunction "2_2") (pintype "passive"))
      (node (ref "R60") (pin "2") (pinfunction "2_2") (pintype "passive"))
      (node (ref "R61") (pin "2") (pinfunction "2_2") (pintype "passive"))
      (node (ref "R62") (pin "2") (pinfunction "2_2") (pintype "passive"))
      (node (ref "R63") (pin "1") (pinfunction "1_1") (pintype "passive"))
      (node (ref "R64") (pin "1") (pinfunction "1_1") (pintype "passive"))
      (node (ref "R65") (pin "1") (pinfunction "1_1") (pintype "passive"))
    )
    (net (code "65") (name "unconnected-(IC4C-IO_L19P_T3_A22_15-PadK13)") (class "Default")
      (node (ref "IC4") (pin "K13") (pinfunction "IO_L19P_T3_A22_15_K13") (pintype "bidirectional+no_connect"))
    )
    (net (code "66") (name "unconnected-(IC11-NC-PadJ1)") (class "Default")
      (node (ref "IC11") (pin "J1") (pinfunction "NC_J1") (pintype "passive+no_connect"))
    )
    (net (code "67") (name "unconnected-(IC11-NC-PadJ9)") (class "Default")
      (node (ref "IC11") (pin "J9") (pinfunction "NC_J9") (pintype "passive+no_connect"))
    )
    (net (code "68") (name "unconnected-(IC11-NC-PadL1)") (class "Default")
      (node (ref "IC11") (pin "L1") (pinfunction "NC_L1") (pintype "passive+no_connect"))
    )
    (net (code "69") (name "unconnected-(IC11-NC-PadL9)") (class "Default")
      (node (ref "IC11") (pin "L9") (pinfunction "NC_L9") (pintype "passive+no_connect"))
    )
    (net (code "70") (name "unconnected-(IC11-NC-PadM7)") (class "Default")
      (node (ref "IC11") (pin "M7") (pinfunction "NC_M7") (pintype "passive+no_connect"))
    )
    (net (code "71") (name "unconnected-(IC35-BYP-Pad4)") (class "Default")
      (node (ref "IC35") (pin "4") (pinfunction "BYP_4") (pintype "passive+no_connect"))
    )
  )
)
